# main.net
KiCad netlist of a schematic drawn in EAGLE
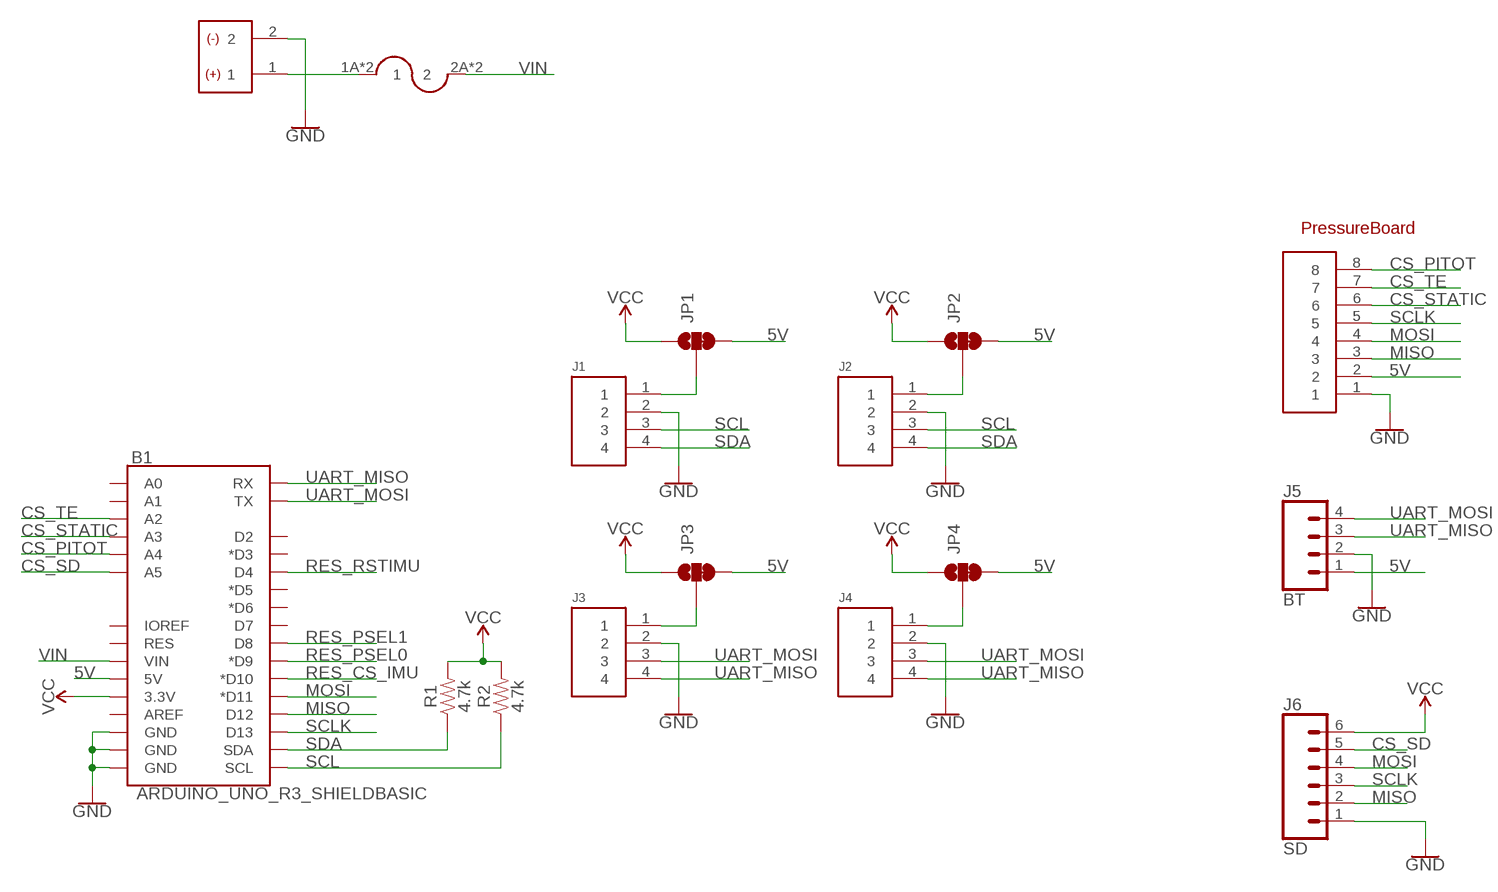
[diagram p0: schematic, sheet 1]

(export (version "E")
  (design (tool "Eeschema 10.0.6"))
  (components
    (comp (ref "B1")
      (value "ARDUINO_UNO_R3_SHIELDBASIC")
      (footprint "eagle-import:UNO_R3_SHIELD")
      (libsource (lib "eagle-import") (part "ARDUINO_UNO_R3_SHIELDBASIC"))
    )
    (comp (ref "J1")
      (value "HEADER4VALULOK")
      (footprint "eagle-import:4PINVALULOK")
      (libsource (lib "eagle-import") (part "HEADER4VALULOK"))
    )
    (comp (ref "J2")
      (value "HEADER4VALULOK")
      (footprint "eagle-import:4PINVALULOK")
      (libsource (lib "eagle-import") (part "HEADER4VALULOK"))
    )
    (comp (ref "J3")
      (value "HEADER4VALULOK")
      (footprint "eagle-import:4PINVALULOK")
      (libsource (lib "eagle-import") (part "HEADER4VALULOK"))
    )
    (comp (ref "J4")
      (value "HEADER4VALULOK")
      (footprint "eagle-import:4PINVALULOK")
      (libsource (lib "eagle-import") (part "HEADER4VALULOK"))
    )
    (comp (ref "J5")
      (value "BT")
      (footprint "eagle-import:1X04_NO_SILK")
      (libsource (lib "eagle-import") (part "CONN_041X04_NO_SILK"))
    )
    (comp (ref "J6")
      (value "SD")
      (footprint "eagle-import:1X06_NO_SILK")
      (libsource (lib "eagle-import") (part "CONN_06NO_SILK_NO_POP"))
    )
    (comp (ref "JP1")
      (value "JUMPER-SMT_3_1-NC_TRACE_SILK")
      (footprint "eagle-import:SMT-JUMPER_3_1-NC_TRACE_SILK")
      (libsource (lib "eagle-import") (part "JUMPER-SMT_3_1-NC_TRACE_SILK"))
    )
    (comp (ref "JP2")
      (value "JUMPER-SMT_3_1-NC_TRACE_SILK")
      (footprint "eagle-import:SMT-JUMPER_3_1-NC_TRACE_SILK")
      (libsource (lib "eagle-import") (part "JUMPER-SMT_3_1-NC_TRACE_SILK"))
    )
    (comp (ref "JP3")
      (value "JUMPER-SMT_3_1-NC_TRACE_SILK")
      (footprint "eagle-import:SMT-JUMPER_3_1-NC_TRACE_SILK")
      (libsource (lib "eagle-import") (part "JUMPER-SMT_3_1-NC_TRACE_SILK"))
    )
    (comp (ref "JP4")
      (value "JUMPER-SMT_3_1-NC_TRACE_SILK")
      (footprint "eagle-import:SMT-JUMPER_3_1-NC_TRACE_SILK")
      (libsource (lib "eagle-import") (part "JUMPER-SMT_3_1-NC_TRACE_SILK"))
    )
    (comp (ref "R1")
      (value "4.7k")
      (footprint "eagle-import:0603")
      (libsource (lib "eagle-import") (part "4.7KOHM-0603-1/10W-1%"))
    )
    (comp (ref "R2")
      (value "4.7k")
      (footprint "eagle-import:0603")
      (libsource (lib "eagle-import") (part "4.7KOHM-0603-1/10W-1%"))
    )
    (comp (ref "U$1")
      (value "PB")
      (footprint "eagle-import:8PINVALULOK")
      (libsource (lib "eagle-import") (part "HEADER8"))
    )
    (comp (ref "U$2")
      (value "FUSE")
      (footprint "eagle-import:AUTO_FUSE")
      (libsource (lib "eagle-import") (part "FUSE"))
    )
    (comp (ref "U$3")
      (value "HEADER2")
      (footprint "eagle-import:2PINVALULOK")
      (libsource (lib "eagle-import") (part "HEADER2"))
    )
  )
  (nets
    (net (code "1") (name "/5V") (class "Default")
      (node (ref "B1") (pin "5V") (pinfunction "5V_5V") (pintype "bidirectional"))
      (node (ref "J5") (pin "1") (pinfunction "1_1") (pintype "passive"))
      (node (ref "JP1") (pin "3") (pinfunction "3_3") (pintype "passive"))
      (node (ref "JP2") (pin "3") (pinfunction "3_3") (pintype "passive"))
      (node (ref "JP3") (pin "3") (pinfunction "3_3") (pintype "passive"))
      (node (ref "JP4") (pin "3") (pinfunction "3_3") (pintype "passive"))
      (node (ref "U$1") (pin "2") (pinfunction "2_2") (pintype "bidirectional"))
    )
    (net (code "2") (name "/CS_PITOT") (class "Default")
      (node (ref "B1") (pin "A4") (pinfunction "A4_A4") (pintype "bidirectional"))
      (node (ref "U$1") (pin "8") (pinfunction "8_8") (pintype "bidirectional"))
    )
    (net (code "3") (name "/CS_SD") (class "Default")
      (node (ref "B1") (pin "A5") (pinfunction "A5_A5") (pintype "bidirectional"))
      (node (ref "J6") (pin "5") (pinfunction "5_5") (pintype "passive"))
    )
    (net (code "4") (name "/CS_STATIC") (class "Default")
      (node (ref "B1") (pin "A3") (pinfunction "A3_A3") (pintype "bidirectional"))
      (node (ref "U$1") (pin "6") (pinfunction "6_6") (pintype "bidirectional"))
    )
    (net (code "5") (name "/CS_TE") (class "Default")
      (node (ref "B1") (pin "A2") (pinfunction "A2_A2") (pintype "bidirectional"))
      (node (ref "U$1") (pin "7") (pinfunction "7_7") (pintype "bidirectional"))
    )
    (net (code "6") (name "/MISO") (class "Default")
      (node (ref "B1") (pin "D12") (pinfunction "D12_D12") (pintype "bidirectional"))
      (node (ref "J6") (pin "2") (pinfunction "2_2") (pintype "passive"))
      (node (ref "U$1") (pin "3") (pinfunction "3_3") (pintype "bidirectional"))
    )
    (net (code "7") (name "/MOSI") (class "Default")
      (node (ref "B1") (pin "D11") (pinfunction "*D11_D11") (pintype "bidirectional"))
      (node (ref "J6") (pin "4") (pinfunction "4_4") (pintype "passive"))
      (node (ref "U$1") (pin "4") (pinfunction "4_4") (pintype "bidirectional"))
    )
    (net (code "8") (name "/RES_CS_IMU") (class "Default")
      (node (ref "B1") (pin "D10") (pinfunction "*D10_D10") (pintype "bidirectional"))
    )
    (net (code "9") (name "/RES_PSEL0") (class "Default")
      (node (ref "B1") (pin "D9") (pinfunction "*D9_D9") (pintype "bidirectional"))
    )
    (net (code "10") (name "/RES_PSEL1") (class "Default")
      (node (ref "B1") (pin "D8") (pinfunction "D8_D8") (pintype "bidirectional"))
    )
    (net (code "11") (name "/RES_RSTIMU") (class "Default")
      (node (ref "B1") (pin "D4") (pinfunction "D4_D4") (pintype "bidirectional"))
    )
    (net (code "12") (name "/SCL") (class "Default")
      (node (ref "B1") (pin "SCL") (pinfunction "SCL_SCL") (pintype "bidirectional"))
      (node (ref "J1") (pin "3") (pinfunction "3_3") (pintype "bidirectional"))
      (node (ref "J2") (pin "3") (pinfunction "3_3") (pintype "bidirectional"))
      (node (ref "R2") (pin "1") (pinfunction "1_1") (pintype "passive"))
    )
    (net (code "13") (name "/SCLK") (class "Default")
      (node (ref "B1") (pin "D13") (pinfunction "D13_D13") (pintype "bidirectional"))
      (node (ref "J6") (pin "3") (pinfunction "3_3") (pintype "passive"))
      (node (ref "U$1") (pin "5") (pinfunction "5_5") (pintype "bidirectional"))
    )
    (net (code "14") (name "/SDA") (class "Default")
      (node (ref "B1") (pin "SDA") (pinfunction "SDA_SDA") (pintype "bidirectional"))
      (node (ref "J1") (pin "4") (pinfunction "4_4") (pintype "bidirectional"))
      (node (ref "J2") (pin "4") (pinfunction "4_4") (pintype "bidirectional"))
      (node (ref "R1") (pin "1") (pinfunction "1_1") (pintype "passive"))
    )
    (net (code "15") (name "/UART_MISO") (class "Default")
      (node (ref "B1") (pin "RX") (pinfunction "RX_RX") (pintype "bidirectional"))
      (node (ref "J3") (pin "4") (pinfunction "4_4") (pintype "bidirectional"))
      (node (ref "J4") (pin "4") (pinfunction "4_4") (pintype "bidirectional"))
      (node (ref "J5") (pin "3") (pinfunction "3_3") (pintype "passive"))
    )
    (net (code "16") (name "/UART_MOSI") (class "Default")
      (node (ref "B1") (pin "TX") (pinfunction "TX_TX") (pintype "bidirectional"))
      (node (ref "J3") (pin "3") (pinfunction "3_3") (pintype "bidirectional"))
      (node (ref "J4") (pin "3") (pinfunction "3_3") (pintype "bidirectional"))
      (node (ref "J5") (pin "4") (pinfunction "4_4") (pintype "passive"))
    )
    (net (code "17") (name "/VIN") (class "Default")
      (node (ref "B1") (pin "VIN") (pinfunction "VIN_VIN") (pintype "bidirectional"))
      (node (ref "U$2") (pin "2A") (pinfunction "2_2A") (pintype "bidirectional"))
      (node (ref "U$2") (pin "2B") (pinfunction "2_2B") (pintype "bidirectional"))
    )
    (net (code "18") (name "GND") (class "Default")
      (node (ref "B1") (pin "GND@0") (pinfunction "GND_GND@0") (pintype "bidirectional"))
      (node (ref "B1") (pin "GND@1") (pinfunction "GND_GND@1") (pintype "bidirectional"))
      (node (ref "B1") (pin "GND@2") (pinfunction "GND_GND@2") (pintype "bidirectional"))
      (node (ref "J1") (pin "2") (pinfunction "2_2") (pintype "bidirectional"))
      (node (ref "J2") (pin "2") (pinfunction "2_2") (pintype "bidirectional"))
      (node (ref "J3") (pin "2") (pinfunction "2_2") (pintype "bidirectional"))
      (node (ref "J4") (pin "2") (pinfunction "2_2") (pintype "bidirectional"))
      (node (ref "J5") (pin "2") (pinfunction "2_2") (pintype "passive"))
      (node (ref "J6") (pin "1") (pinfunction "1_1") (pintype "passive"))
      (node (ref "U$1") (pin "1") (pinfunction "1_1") (pintype "bidirectional"))
      (node (ref "U$3") (pin "2") (pinfunction "2_2") (pintype "bidirectional"))
    )
    (net (code "19") (name "Net-(J1-Pad1)") (class "Default")
      (node (ref "J1") (pin "1") (pinfunction "1_1") (pintype "bidirectional"))
      (node (ref "JP1") (pin "2") (pinfunction "2_2") (pintype "passive"))
    )
    (net (code "20") (name "Net-(J2-Pad1)") (class "Default")
      (node (ref "J2") (pin "1") (pinfunction "1_1") (pintype "bidirectional"))
      (node (ref "JP2") (pin "2") (pinfunction "2_2") (pintype "passive"))
    )
    (net (code "21") (name "Net-(J3-Pad1)") (class "Default")
      (node (ref "J3") (pin "1") (pinfunction "1_1") (pintype "bidirectional"))
      (node (ref "JP3") (pin "2") (pinfunction "2_2") (pintype "passive"))
    )
    (net (code "22") (name "Net-(J4-Pad1)") (class "Default")
      (node (ref "J4") (pin "1") (pinfunction "1_1") (pintype "bidirectional"))
      (node (ref "JP4") (pin "2") (pinfunction "2_2") (pintype "passive"))
    )
    (net (code "23") (name "Net-(U$2-1-Pad1A)") (class "Default")
      (node (ref "U$2") (pin "1A") (pinfunction "1_1A") (pintype "bidirectional"))
      (node (ref "U$2") (pin "1B") (pinfunction "1_1B") (pintype "bidirectional"))
      (node (ref "U$3") (pin "1") (pinfunction "1_1") (pintype "bidirectional"))
    )
    (net (code "24") (name "VCC") (class "Default")
      (node (ref "B1") (pin "3.3V") (pinfunction "3.3V_3.3V") (pintype "bidirectional"))
      (node (ref "J6") (pin "6") (pinfunction "6_6") (pintype "passive"))
      (node (ref "JP1") (pin "1") (pinfunction "1_1") (pintype "passive"))
      (node (ref "JP2") (pin "1") (pinfunction "1_1") (pintype "passive"))
      (node (ref "JP3") (pin "1") (pinfunction "1_1") (pintype "passive"))
      (node (ref "JP4") (pin "1") (pinfunction "1_1") (pintype "passive"))
      (node (ref "R1") (pin "2") (pinfunction "2_2") (pintype "passive"))
      (node (ref "R2") (pin "2") (pinfunction "2_2") (pintype "passive"))
    )
    (net (code "25") (name "unconnected-(B1-*D3-PadD3)") (class "Default")
      (node (ref "B1") (pin "D3") (pinfunction "*D3_D3") (pintype "bidirectional"))
    )
    (net (code "26") (name "unconnected-(B1-*D5-PadD5)") (class "Default")
      (node (ref "B1") (pin "D5") (pinfunction "*D5_D5") (pintype "bidirectional"))
    )
    (net (code "27") (name "unconnected-(B1-*D6-PadD6)") (class "Default")
      (node (ref "B1") (pin "D6") (pinfunction "*D6_D6") (pintype "bidirectional"))
    )
    (net (code "28") (name "unconnected-(B1-PadA0)") (class "Default")
      (node (ref "B1") (pin "A0") (pinfunction "A0_A0") (pintype "bidirectional"))
    )
    (net (code "29") (name "unconnected-(B1-PadA1)") (class "Default")
      (node (ref "B1") (pin "A1") (pinfunction "A1_A1") (pintype "bidirectional"))
    )
    (net (code "30") (name "unconnected-(B1-PadAREF)") (class "Default")
      (node (ref "B1") (pin "AREF") (pinfunction "AREF_AREF") (pintype "bidirectional"))
    )
    (net (code "31") (name "unconnected-(B1-PadD2)") (class "Default")
      (node (ref "B1") (pin "D2") (pinfunction "D2_D2") (pintype "bidirectional"))
    )
    (net (code "32") (name "unconnected-(B1-PadD7)") (class "Default")
      (node (ref "B1") (pin "D7") (pinfunction "D7_D7") (pintype "bidirectional"))
    )
    (net (code "33") (name "unconnected-(B1-PadIOREF)") (class "Default")
      (node (ref "B1") (pin "IOREF") (pinfunction "IOREF_IOREF") (pintype "bidirectional"))
    )
    (net (code "34") (name "unconnected-(B1-PadRES)") (class "Default")
      (node (ref "B1") (pin "RES") (pinfunction "RES_RES") (pintype "bidirectional"))
    )
  )
)
